# LT3080.net
KiCad netlist of a schematic drawn in Altium Designer
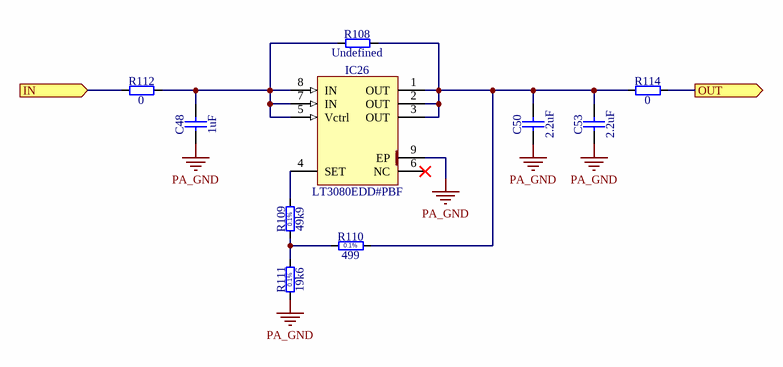
[diagram p0: LT3080.SchDoc]

(export (version "E")
  (design (tool "Eeschema 10.0.6"))
  (components
    (comp (ref "C48")
      (value "1uF")
      (footprint "CAPC1608X87N")
      (description "Non-polarised capacitor")
      (fields
        (field (name "PART NUMBER") "CC0603_1UF_50V_10%_X5R")
        (field (name "VOLTAGE") "50V")
        (field (name "AUTHOR") "CERN DEM JMW")
      )
      (libsource (lib "Capacitors") (part "Capacitor - non polarized"))
    )
    (comp (ref "C50")
      (value "2.2uF")
      (footprint "CAPC2012X140N")
      (description "Non-polarised capacitor")
      (fields
        (field (name "PART NUMBER") "CC0805_2.2UF_50V_10%_X7R")
        (field (name "VOLTAGE") "50V")
        (field (name "AUTHOR") "CERN DEM JLC")
      )
      (libsource (lib "Capacitors") (part "Capacitor - non polarized"))
    )
    (comp (ref "C53")
      (value "2.2uF")
      (footprint "CAPC2012X140N")
      (description "Non-polarised capacitor")
      (fields
        (field (name "PART NUMBER") "CC0805_2.2UF_50V_10%_X7R")
        (field (name "VOLTAGE") "50V")
        (field (name "AUTHOR") "CERN DEM JLC")
      )
      (libsource (lib "Capacitors") (part "Capacitor - non polarized"))
    )
    (comp (ref "IC26")
      (value "LT3080EDD#PBF")
      (footprint "SON50P300X300X80-9N-R175X248")
      (description "Adjustable 1.1A Single Resistor Low Dropout Regulator")
      (fields (field (name "MANUFACTURER") "LINEAR TECHNOLOGY") (field (name "AUTHOR") "CERN DEM JLC"))
      (libsource (lib "ICs And Semiconductors") (part "LT3080EDD"))
    )
    (comp (ref "R108")
      (value "Undefined")
      (footprint "RESC3216X65N")
      (description "Resistor")
      (fields (field (name "PART NUMBER") "R1206_NO-VALUE") (field (name "AUTHOR") "CERN DEM JLC"))
      (libsource (lib "Resistors") (part "Resistor"))
    )
    (comp (ref "R109")
      (value "49k9")
      (footprint "RESC1608X55N")
      (description "Resistor - 0.1%")
      (fields
        (field (name "PART NUMBER") "R0603_49K9_0.1%_0.063W_10PPM")
        (field (name "POWER") "0.063W")
        (field (name "AUTHOR") "CERN DEM JLC")
      )
      (libsource (lib "Resistors") (part "Resistor - 0.1%"))
    )
    (comp (ref "R110")
      (value "499")
      (footprint "RESC1608X55N")
      (description "Resistor - 0.1%")
      (fields
        (field (name "PART NUMBER") "R0603_499R_0.1%_0.063W_10PPM")
        (field (name "POWER") "0.063W")
        (field (name "AUTHOR") "CERN DEM JLC")
      )
      (libsource (lib "Resistors") (part "Resistor - 0.1%"))
    )
    (comp (ref "R111")
      (value "19k6")
      (footprint "RESC1608X55N")
      (description "Resistor - 0.1%")
      (fields
        (field (name "PART NUMBER") "R0603_19K6_0.1%_0.063W_10PPM")
        (field (name "POWER") "0.063W")
        (field (name "AUTHOR") "CERN DEM JLC")
      )
      (libsource (lib "Resistors") (part "Resistor - 0.1%"))
    )
    (comp (ref "R112")
      (value "0")
      (footprint "RESC3216X65N")
      (description "Resistor")
      (fields
        (field (name "PART NUMBER") "R1206_0R_JUMPER")
        (field (name "MANUFACTURER") "GENERIC")
        (field (name "AUTHOR") "CERN DEM JLC")
      )
      (libsource (lib "Resistors") (part "Resistor"))
    )
    (comp (ref "R114")
      (value "0")
      (footprint "RESC3216X65N")
      (description "Resistor")
      (fields
        (field (name "PART NUMBER") "R1206_0R_JUMPER")
        (field (name "MANUFACTURER") "GENERIC")
        (field (name "AUTHOR") "CERN DEM JLC")
      )
      (libsource (lib "Resistors") (part "Resistor"))
    )
  )
  (nets
    (net (code "1") (name "/IN") (class "Default")
      (node (ref "R112") (pin "1") (pinfunction "1_1") (pintype "passive"))
    )
    (net (code "2") (name "/OUT") (class "Default")
      (node (ref "R114") (pin "2") (pinfunction "2_2") (pintype "passive"))
    )
    (net (code "3") (name "Net-(C50-Pad2)") (class "Default")
      (node (ref "C50") (pin "2") (pinfunction "2_2") (pintype "passive"))
      (node (ref "C53") (pin "2") (pinfunction "2_2") (pintype "passive"))
      (node (ref "IC26") (pin "1") (pinfunction "OUT_1") (pintype "power_in"))
      (node (ref "IC26") (pin "2") (pinfunction "OUT_2") (pintype "power_in"))
      (node (ref "IC26") (pin "3") (pinfunction "OUT_3") (pintype "power_in"))
      (node (ref "R108") (pin "2") (pinfunction "2_2") (pintype "passive"))
      (node (ref "R110") (pin "2") (pinfunction "2_2") (pintype "passive"))
      (node (ref "R114") (pin "1") (pinfunction "1_1") (pintype "passive"))
    )
    (net (code "4") (name "Net-(IC26-SET)") (class "Default")
      (node (ref "IC26") (pin "4") (pinfunction "SET_4") (pintype "passive"))
      (node (ref "R109") (pin "2") (pinfunction "2_2") (pintype "passive"))
    )
    (net (code "5") (name "Net-(IC26-Vctrl)") (class "Default")
      (node (ref "C48") (pin "2") (pinfunction "2_2") (pintype "passive"))
      (node (ref "IC26") (pin "5") (pinfunction "Vctrl_5") (pintype "input"))
      (node (ref "IC26") (pin "7") (pinfunction "IN_7") (pintype "input"))
      (node (ref "IC26") (pin "8") (pinfunction "IN_8") (pintype "input"))
      (node (ref "R108") (pin "1") (pinfunction "1_1") (pintype "passive"))
      (node (ref "R112") (pin "2") (pinfunction "2_2") (pintype "passive"))
    )
    (net (code "6") (name "Net-(R109-Pad1)") (class "Default")
      (node (ref "R109") (pin "1") (pinfunction "1_1") (pintype "passive"))
      (node (ref "R110") (pin "1") (pinfunction "1_1") (pintype "passive"))
      (node (ref "R111") (pin "2") (pinfunction "2_2") (pintype "passive"))
    )
    (net (code "7") (name "PA_GND") (class "Default")
      (node (ref "C48") (pin "1") (pinfunction "1_1") (pintype "passive"))
      (node (ref "C50") (pin "1") (pinfunction "1_1") (pintype "passive"))
      (node (ref "C53") (pin "1") (pinfunction "1_1") (pintype "passive"))
      (node (ref "IC26") (pin "9") (pinfunction "EP_9") (pintype "power_in"))
      (node (ref "R111") (pin "1") (pinfunction "1_1") (pintype "passive"))
    )
    (net (code "8") (name "unconnected-(IC26-NC-Pad6)") (class "Default")
      (node (ref "IC26") (pin "6") (pinfunction "NC_6") (pintype "passive+no_connect"))
    )
  )
)
